# Display.net
KiCad netlist of a schematic drawn in Altium Designer
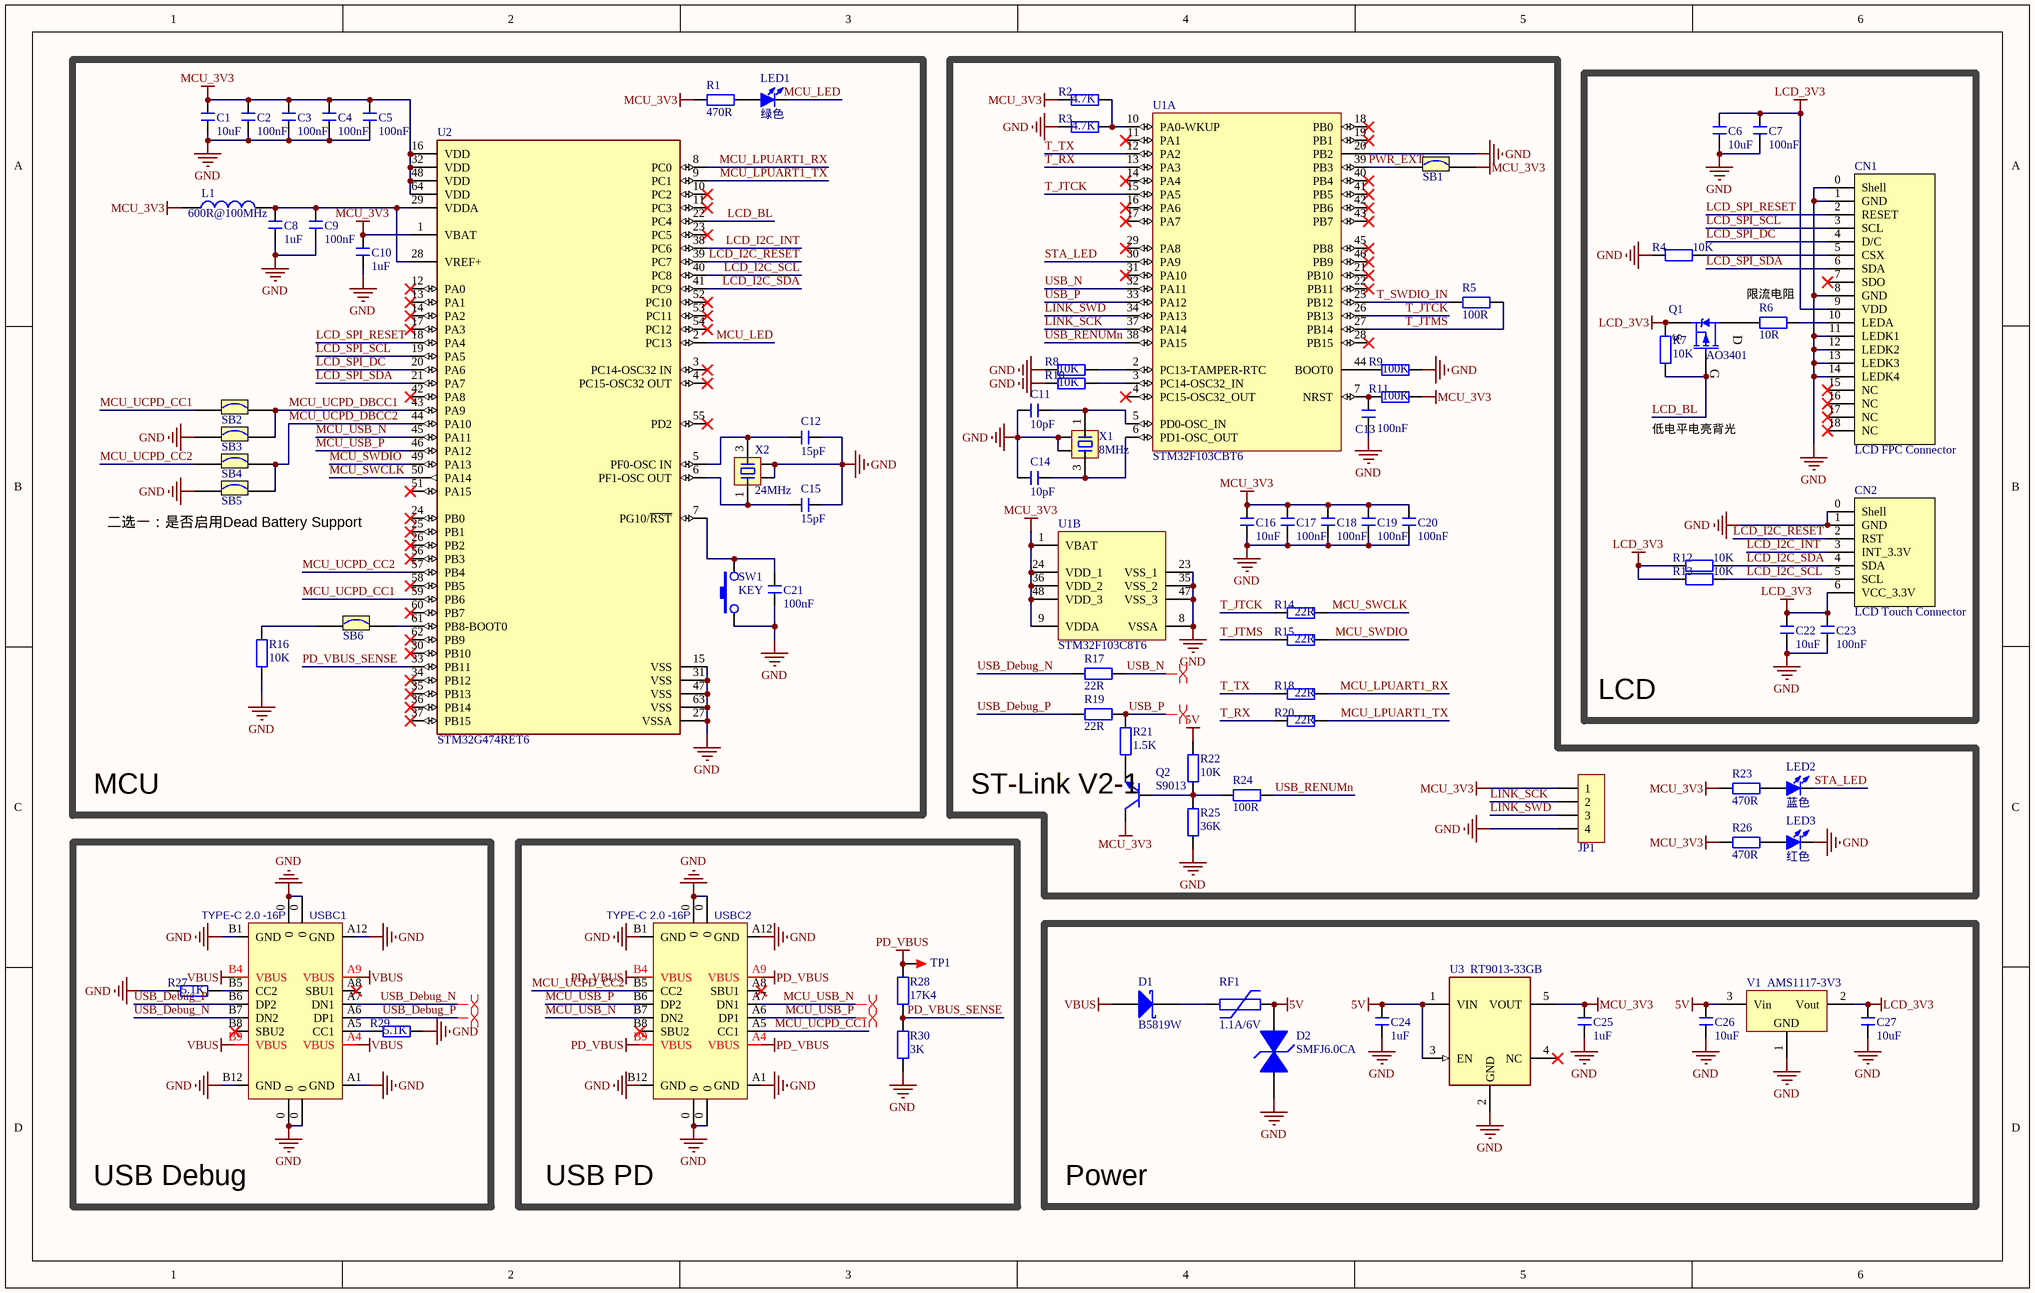
[diagram p0: Display.SchDoc]

(export (version "E")
  (design (tool "Eeschema 10.0.6"))
  (components
    (comp (ref "C1")
      (value "10uF")
      (footprint "C 0402_L")
      (description "无极性贴片电容")
      (fields (field (name "版权归属") "源创客"))
      (libsource (lib "源创客") (part "C"))
    )
    (comp (ref "C2")
      (value "100nF")
      (footprint "C 0402_L")
      (description "无极性贴片电容")
      (fields (field (name "版权归属") "源创客"))
      (libsource (lib "源创客") (part "C"))
    )
    (comp (ref "C3")
      (value "100nF")
      (footprint "C 0402_L")
      (description "无极性贴片电容")
      (fields (field (name "版权归属") "源创客"))
      (libsource (lib "源创客") (part "C"))
    )
    (comp (ref "C4")
      (value "100nF")
      (footprint "C 0402_L")
      (description "无极性贴片电容")
      (fields (field (name "版权归属") "源创客"))
      (libsource (lib "源创客") (part "C"))
    )
    (comp (ref "C5")
      (value "100nF")
      (footprint "C 0402_L")
      (description "无极性贴片电容")
      (fields (field (name "版权归属") "源创客"))
      (libsource (lib "源创客") (part "C"))
    )
    (comp (ref "C6")
      (value "10uF")
      (footprint "C 0402_L")
      (description "无极性贴片电容")
      (fields (field (name "版权归属") "源创客"))
      (libsource (lib "源创客") (part "C"))
    )
    (comp (ref "C7")
      (value "100nF")
      (footprint "C 0402_L")
      (description "无极性贴片电容")
      (fields (field (name "版权归属") "源创客"))
      (libsource (lib "源创客") (part "C"))
    )
    (comp (ref "C8")
      (value "1uF")
      (footprint "C 0402_L")
      (description "无极性贴片电容")
      (fields (field (name "版权归属") "源创客"))
      (libsource (lib "源创客") (part "C"))
    )
    (comp (ref "C9")
      (value "100nF")
      (footprint "C 0402_L")
      (description "无极性贴片电容")
      (fields (field (name "版权归属") "源创客"))
      (libsource (lib "源创客") (part "C"))
    )
    (comp (ref "C10")
      (value "1uF")
      (footprint "C 0402_L")
      (description "无极性贴片电容")
      (fields (field (name "版权归属") "源创客"))
      (libsource (lib "源创客") (part "C"))
    )
    (comp (ref "C11")
      (value "10pF")
      (footprint "C 0402_L")
      (description "无极性贴片电容")
      (fields (field (name "版权归属") "源创客"))
      (libsource (lib "源创客") (part "C"))
    )
    (comp (ref "C12")
      (value "15pF")
      (footprint "C 0402_L")
      (description "无极性贴片电容")
      (fields (field (name "版权归属") "源创客"))
      (libsource (lib "源创客") (part "C"))
    )
    (comp (ref "C13")
      (value "100nF")
      (footprint "C 0402_L")
      (description "无极性贴片电容")
      (fields (field (name "版权归属") "源创客"))
      (libsource (lib "源创客") (part "C"))
    )
    (comp (ref "C14")
      (value "10pF")
      (footprint "C 0402_L")
      (description "无极性贴片电容")
      (fields (field (name "版权归属") "源创客"))
      (libsource (lib "源创客") (part "C"))
    )
    (comp (ref "C15")
      (value "15pF")
      (footprint "C 0402_L")
      (description "无极性贴片电容")
      (fields (field (name "版权归属") "源创客"))
      (libsource (lib "源创客") (part "C"))
    )
    (comp (ref "C16")
      (value "10uF")
      (footprint "C 0402_L")
      (description "无极性贴片电容")
      (fields (field (name "版权归属") "源创客"))
      (libsource (lib "源创客") (part "C"))
    )
    (comp (ref "C17")
      (value "100nF")
      (footprint "C 0402_L")
      (description "无极性贴片电容")
      (fields (field (name "版权归属") "源创客"))
      (libsource (lib "源创客") (part "C"))
    )
    (comp (ref "C18")
      (value "100nF")
      (footprint "C 0402_L")
      (description "无极性贴片电容")
      (fields (field (name "版权归属") "源创客"))
      (libsource (lib "源创客") (part "C"))
    )
    (comp (ref "C19")
      (value "100nF")
      (footprint "C 0402_L")
      (description "无极性贴片电容")
      (fields (field (name "版权归属") "源创客"))
      (libsource (lib "源创客") (part "C"))
    )
    (comp (ref "C20")
      (value "100nF")
      (footprint "C 0402_L")
      (description "无极性贴片电容")
      (fields (field (name "版权归属") "源创客"))
      (libsource (lib "源创客") (part "C"))
    )
    (comp (ref "C21")
      (value "100nF")
      (footprint "C 0402_L")
      (description "无极性贴片电容")
      (fields (field (name "版权归属") "源创客"))
      (libsource (lib "源创客") (part "C"))
    )
    (comp (ref "C22")
      (value "10uF")
      (footprint "C 0402_L")
      (description "无极性贴片电容")
      (fields (field (name "版权归属") "源创客"))
      (libsource (lib "源创客") (part "C"))
    )
    (comp (ref "C23")
      (value "100nF")
      (footprint "C 0402_L")
      (description "无极性贴片电容")
      (fields (field (name "版权归属") "源创客"))
      (libsource (lib "源创客") (part "C"))
    )
    (comp (ref "C24")
      (value "1uF")
      (footprint "C 0402_L")
      (description "无极性贴片电容")
      (fields (field (name "版权归属") "源创客"))
      (libsource (lib "源创客") (part "C"))
    )
    (comp (ref "C25")
      (value "1uF")
      (footprint "C 0402_L")
      (description "无极性贴片电容")
      (fields (field (name "版权归属") "源创客"))
      (libsource (lib "源创客") (part "C"))
    )
    (comp (ref "C26")
      (value "10uF")
      (footprint "C 0402_L")
      (description "无极性贴片电容")
      (fields (field (name "版权归属") "源创客"))
      (libsource (lib "源创客") (part "C"))
    )
    (comp (ref "C27")
      (value "10uF")
      (footprint "C 0402_L")
      (description "无极性贴片电容")
      (fields (field (name "版权归属") "源创客"))
      (libsource (lib "源创客") (part "C"))
    )
    (comp (ref "CN1")
      (value "LCD FPC Connector")
      (footprint "FPC_Connector_0.5mm_18P")
      (description "2.8英寸TFT-LCD电容触摸屏接插式FPC座子")
      (libsource (lib "Display") (part "LCD"))
    )
    (comp (ref "CN2")
      (value "LCD Touch Connector")
      (footprint "FPC_Connector_0.5mm_6P")
      (description "2.8英寸TFT-LCD电容触摸屏触摸检测芯片接插式FPC座子")
      (libsource (lib "Display") (part "Touch"))
    )
    (comp (ref "D1")
      (value "B5819W")
      (footprint "MCC-SOD123_V")
      (description "Schottky Barrier Rectifier, 1 A, 40 Vrm, -65 to 125 degC, 2-Pin SOD123, RoHS, Tape and Reel")
      (fields (field (name "MANUFACTURER") "Micro Commercial Components"))
      (libsource (lib "Altium Content Vault") (part "DSKY-AK-2"))
    )
    (comp (ref "D2")
      (value "SMFJ6.0CA")
      (footprint "SMFJ6.0CA")
      (description "贴片TVS瞬变抑制二极管")
      (libsource (lib "Display") (part "SMFJ6.0CA"))
    )
    (comp (ref "JP1")
      (value "HDR-1X4")
      (footprint "HDR2.54-LI-4P")
      (description "4P接插件")
      (libsource (lib "5.5 - 2.54mm(100mil)连接器(XH2.54)") (part "Header 4"))
    )
    (comp (ref "L1")
      (value "600R@100MHz")
      (footprint "L 0603")
      (description "小功率贴片电感")
      (fields (field (name "版权归属") "源创客"))
      (libsource (lib "源创客") (part "L"))
    )
    (comp (ref "LED1")
      (value "绿色")
      (footprint "LED 0603G")
      (description "贴片LED")
      (fields (field (name "版权归属") "源创客"))
      (libsource (lib "源创客") (part "LED-SMD"))
    )
    (comp (ref "LED2")
      (value "蓝色")
      (footprint "LED 0603B")
      (description "贴片LED")
      (fields (field (name "版权归属") "源创客"))
      (libsource (lib "源创客") (part "LED-SMD"))
    )
    (comp (ref "LED3")
      (value "红色")
      (footprint "LED 0603R")
      (description "贴片LED")
      (fields (field (name "版权归属") "源创客"))
      (libsource (lib "源创客") (part "LED-SMD"))
    )
    (comp (ref "Q1")
      (value "AO3401")
      (footprint "SOT23-3L")
      (description "P沟道 30V/4.2A")
      (libsource (lib "0.4 - 三极管-场效应管-可控硅") (part "AO3401"))
    )
    (comp (ref "Q2")
      (value "S9013")
      (footprint "SOT23-3L")
      (description "低频放大-NPN型")
      (fields (field (name "版权归属") "源创客"))
      (libsource (lib "源创客") (part "9013-SMD"))
    )
    (comp (ref "R1")
      (value "470R")
      (footprint "R 0402_L")
      (description "贴片电阻")
      (fields (field (name "版权归属") "源创客"))
      (libsource (lib "源创客") (part "R"))
    )
    (comp (ref "R2")
      (value "4.7K")
      (footprint "R 0402_L")
      (description "贴片电阻")
      (fields (field (name "版权归属") "源创客"))
      (libsource (lib "源创客") (part "R"))
    )
    (comp (ref "R3")
      (value "4.7K")
      (footprint "R 0402_L")
      (description "贴片电阻")
      (fields (field (name "版权归属") "源创客"))
      (libsource (lib "源创客") (part "R"))
    )
    (comp (ref "R4")
      (value "10K")
      (footprint "R 0402_L")
      (description "贴片电阻")
      (fields (field (name "版权归属") "源创客"))
      (libsource (lib "源创客") (part "R"))
    )
    (comp (ref "R5")
      (value "100R")
      (footprint "R 0402_L")
      (description "贴片电阻")
      (fields (field (name "版权归属") "源创客"))
      (libsource (lib "源创客") (part "R"))
    )
    (comp (ref "R6")
      (value "10R")
      (footprint "R 0402_L")
      (description "贴片电阻")
      (fields (field (name "版权归属") "源创客"))
      (libsource (lib "源创客") (part "R"))
    )
    (comp (ref "R7")
      (value "10K")
      (footprint "R 0402_L")
      (description "贴片电阻")
      (fields (field (name "版权归属") "源创客"))
      (libsource (lib "源创客") (part "R"))
    )
    (comp (ref "R8")
      (value "10K")
      (footprint "R 0402_L")
      (description "贴片电阻")
      (fields (field (name "版权归属") "源创客"))
      (libsource (lib "源创客") (part "R"))
    )
    (comp (ref "R9")
      (value "100K")
      (footprint "R 0402_L")
      (description "贴片电阻")
      (fields (field (name "版权归属") "源创客"))
      (libsource (lib "源创客") (part "R"))
    )
    (comp (ref "R10")
      (value "10K")
      (footprint "R 0402_L")
      (description "贴片电阻")
      (fields (field (name "版权归属") "源创客"))
      (libsource (lib "源创客") (part "R"))
    )
    (comp (ref "R11")
      (value "100K")
      (footprint "R 0402_L")
      (description "贴片电阻")
      (fields (field (name "版权归属") "源创客"))
      (libsource (lib "源创客") (part "R"))
    )
    (comp (ref "R12")
      (value "10K")
      (footprint "R 0402_L")
      (description "贴片电阻")
      (fields (field (name "版权归属") "源创客"))
      (libsource (lib "源创客") (part "R"))
    )
    (comp (ref "R13")
      (value "10K")
      (footprint "R 0402_L")
      (description "贴片电阻")
      (fields (field (name "版权归属") "源创客"))
      (libsource (lib "源创客") (part "R"))
    )
    (comp (ref "R14")
      (value "22R")
      (footprint "R 0402_L")
      (description "贴片电阻")
      (fields (field (name "版权归属") "源创客"))
      (libsource (lib "源创客") (part "R"))
    )
    (comp (ref "R15")
      (value "22R")
      (footprint "R 0402_L")
      (description "贴片电阻")
      (fields (field (name "版权归属") "源创客"))
      (libsource (lib "源创客") (part "R"))
    )
    (comp (ref "R16")
      (value "10K")
      (footprint "R 0402_L")
      (description "贴片电阻")
      (fields (field (name "版权归属") "源创客"))
      (libsource (lib "源创客") (part "R"))
    )
    (comp (ref "R17")
      (value "22R")
      (footprint "R 0402_L")
      (description "贴片电阻")
      (fields (field (name "版权归属") "源创客"))
      (libsource (lib "源创客") (part "R"))
    )
    (comp (ref "R18")
      (value "22R")
      (footprint "R 0402_L")
      (description "贴片电阻")
      (fields (field (name "版权归属") "源创客"))
      (libsource (lib "源创客") (part "R"))
    )
    (comp (ref "R19")
      (value "22R")
      (footprint "R 0402_L")
      (description "贴片电阻")
      (fields (field (name "版权归属") "源创客"))
      (libsource (lib "源创客") (part "R"))
    )
    (comp (ref "R20")
      (value "22R")
      (footprint "R 0402_L")
      (description "贴片电阻")
      (fields (field (name "版权归属") "源创客"))
      (libsource (lib "源创客") (part "R"))
    )
    (comp (ref "R21")
      (value "1.5K")
      (footprint "R 0402_L")
      (description "贴片电阻")
      (fields (field (name "版权归属") "源创客"))
      (libsource (lib "源创客") (part "R"))
    )
    (comp (ref "R22")
      (value "10K")
      (footprint "R 0402_L")
      (description "贴片电阻")
      (fields (field (name "版权归属") "源创客"))
      (libsource (lib "源创客") (part "R"))
    )
    (comp (ref "R23")
      (value "470R")
      (footprint "R 0402_L")
      (description "贴片电阻")
      (fields (field (name "版权归属") "源创客"))
      (libsource (lib "源创客") (part "R"))
    )
    (comp (ref "R24")
      (value "100R")
      (footprint "R 0402_L")
      (description "贴片电阻")
      (fields (field (name "版权归属") "源创客"))
      (libsource (lib "源创客") (part "R"))
    )
    (comp (ref "R25")
      (value "36K")
      (footprint "R 0402_L")
      (description "贴片电阻")
      (fields (field (name "版权归属") "源创客"))
      (libsource (lib "源创客") (part "R"))
    )
    (comp (ref "R26")
      (value "470R")
      (footprint "R 0402_L")
      (description "贴片电阻")
      (fields (field (name "版权归属") "源创客"))
      (libsource (lib "源创客") (part "R"))
    )
    (comp (ref "R27")
      (value "5.1K")
      (footprint "R 0402_L")
      (description "贴片电阻")
      (fields (field (name "版权归属") "源创客"))
      (libsource (lib "源创客") (part "R"))
    )
    (comp (ref "R28")
      (value "17K4")
      (footprint "R 0402_L")
      (description "贴片电阻")
      (fields (field (name "版权归属") "源创客"))
      (libsource (lib "源创客") (part "R"))
    )
    (comp (ref "R29")
      (value "5.1K")
      (footprint "R 0402_L")
      (description "贴片电阻")
      (fields (field (name "版权归属") "源创客"))
      (libsource (lib "源创客") (part "R"))
    )
    (comp (ref "R30")
      (value "3K")
      (footprint "R 0402_L")
      (description "贴片电阻")
      (fields (field (name "版权归属") "源创客"))
      (libsource (lib "源创客") (part "R"))
    )
    (comp (ref "RF1")
      (value "1.1A/6V")
      (footprint "MF-NSMF110-2")
      (description "PPTC自恢复保险丝")
      (fields (field (name "版权归属") "源创客"))
      (libsource (lib "源创客") (part "PPTC"))
    )
    (comp (ref "SB1")
      (value "SelectBit")
      (footprint "SelectBit 0402")
      (description "跨接桥，用于选择不同的模式，可以用锡连上，或者焊上0R电阻")
      (libsource (lib "Display") (part "SelectBit"))
    )
    (comp (ref "SB2")
      (value "SelectBit")
      (footprint "SelectBit 0402")
      (description "跨接桥，用于选择不同的模式，可以用锡连上，或者焊上0R电阻")
      (libsource (lib "Display") (part "SelectBit"))
    )
    (comp (ref "SB3")
      (value "SelectBit")
      (footprint "SelectBit 0402")
      (description "跨接桥，用于选择不同的模式，可以用锡连上，或者焊上0R电阻")
      (libsource (lib "Display") (part "SelectBit"))
    )
    (comp (ref "SB4")
      (value "SelectBit")
      (footprint "SelectBit 0402")
      (description "跨接桥，用于选择不同的模式，可以用锡连上，或者焊上0R电阻")
      (libsource (lib "Display") (part "SelectBit"))
    )
    (comp (ref "SB5")
      (value "SelectBit")
      (footprint "SelectBit 0402")
      (description "跨接桥，用于选择不同的模式，可以用锡连上，或者焊上0R电阻")
      (libsource (lib "Display") (part "SelectBit"))
    )
    (comp (ref "SB6")
      (value "SelectBit")
      (footprint "SelectBit 0402")
      (description "跨接桥，用于选择不同的模式，可以用锡连上，或者焊上0R电阻")
      (libsource (lib "Display") (part "SelectBit"))
    )
    (comp (ref "SW1")
      (value "KEY")
      (footprint "小乌龟2脚轻触开关3.9*2.9")
      (description "轻触开关")
      (libsource (lib "轻触开关") (part "KEY"))
    )
    (comp (ref "TP1")
      (value "TEST TP")
      (footprint "TEST TP1.4_R")
      (description "测试环")
      (fields (field (name "版权归属") "源创客"))
      (libsource (lib "源创客") (part "TEST TP"))
    )
    (comp (ref "U1")
      (value "STM32F103CBT6")
      (footprint "STM-LQFP48_L")
      (fields (field (name "PARTNUMBER") "STM32F103C8T6"))
      (libsource (lib "Altium Content Vault") (part "MC-ARM-STM32F103X8_B-SQ48"))
    )
    (comp (ref "U2")
      (value "STM32G474RET6")
      (footprint "FP-LQFP64-5W-MFG")
      (description "MAINSTREAM ARM CORTEX-M4 CORE WI")
      (fields
        (field (name "MANUFACTURER") "STMicroelectronics")
        (field (name "OCTOPART") "https://octopart.com/stm32g474ret6-stmicroelectronics-102308483")
      )
      (libsource (lib "Altium Content Vault") (part "f7e4c2ab6713028e27effac94efeea5"))
    )
    (comp (ref "U3")
      (value "RT9013-33GB")
      (footprint "SOT94P279X129-5N")
      (description "Linear Voltage Regulator IC 1 Output 500mA SOT-23-5")
      (fields (field (name "MF") "Richtek USA"))
      (libsource (lib "Display") (part "RT9013-33GB"))
    )
    (comp (ref "USBC1")
      (value "TYPE-C 2.0 -16P")
      (footprint "USB-C-SMD_16P")
      (description "USB2.0_Type-C_16Pin母座")
      (libsource (lib "0.6 - 电源-以太网-音频-Type-C USB插座") (part "USB2.0_Type-C_16Pin"))
    )
    (comp (ref "USBC2")
      (value "TYPE-C 2.0 -16P")
      (footprint "USB-C-SMD_16P")
      (description "USB2.0_Type-C_16Pin母座")
      (libsource (lib "0.6 - 电源-以太网-音频-Type-C USB插座") (part "USB2.0_Type-C_16Pin"))
    )
    (comp (ref "V1")
      (value "AMS1117-3V3")
      (footprint "SOT89_L")
      (description "三端稳压芯片")
      (fields (field (name "版权归属") "源创客"))
      (libsource (lib "源创客") (part "AMS1117"))
    )
    (comp (ref "X1")
      (value "8MHz")
      (footprint "XTAL-3225-4P")
      (description "4脚无源晶振(谐振器）")
      (libsource (lib "0.1 - 电阻-电容-电感-晶振-晶体-磁珠-电位器") (part "XTAL-4P"))
    )
    (comp (ref "X2")
      (value "24MHz")
      (footprint "XTAL-3225-4P")
      (description "4脚无源晶振(谐振器）")
      (libsource (lib "") (part "XTAL-4P_1"))
    )
  )
  (nets
    (net (code "1") (name "/LCD_BL") (class "Default")
      (node (ref "Q1") (pin "1") (pinfunction "G_1") (pintype "passive"))
      (node (ref "R7") (pin "1") (pinfunction "1_1") (pintype "passive"))
      (node (ref "U2") (pin "22") (pinfunction "PC4_22") (pintype "bidirectional"))
    )
    (net (code "2") (name "/LCD_I2C_INT") (class "Default")
      (node (ref "CN2") (pin "3") (pinfunction "INT_3.3V_3") (pintype "passive"))
      (node (ref "U2") (pin "38") (pinfunction "PC6_38") (pintype "bidirectional"))
    )
    (net (code "3") (name "/LCD_I2C_RESET") (class "Default")
      (node (ref "CN2") (pin "2") (pinfunction "RST_2") (pintype "passive"))
      (node (ref "U2") (pin "39") (pinfunction "PC7_39") (pintype "bidirectional"))
    )
    (net (code "4") (name "/LCD_I2C_SCL") (class "Default")
      (node (ref "CN2") (pin "5") (pinfunction "SCL_5") (pintype "passive"))
      (node (ref "R13") (pin "1") (pinfunction "1_1") (pintype "passive"))
      (node (ref "U2") (pin "40") (pinfunction "PC8_40") (pintype "bidirectional"))
    )
    (net (code "5") (name "/LCD_I2C_SDA") (class "Default")
      (node (ref "CN2") (pin "4") (pinfunction "SDA_4") (pintype "passive"))
      (node (ref "R12") (pin "1") (pinfunction "1_1") (pintype "passive"))
      (node (ref "U2") (pin "41") (pinfunction "PC9_41") (pintype "bidirectional"))
    )
    (net (code "6") (name "/LCD_SPI_DC") (class "Default")
      (node (ref "CN1") (pin "4") (pinfunction "D/C_4") (pintype "passive"))
      (node (ref "U2") (pin "20") (pinfunction "PA6_20") (pintype "bidirectional"))
    )
    (net (code "7") (name "/LCD_SPI_RESET") (class "Default")
      (node (ref "CN1") (pin "2") (pinfunction "RESET_2") (pintype "passive"))
      (node (ref "U2") (pin "18") (pinfunction "PA4_18") (pintype "bidirectional"))
    )
    (net (code "8") (name "/LCD_SPI_SCL") (class "Default")
      (node (ref "CN1") (pin "3") (pinfunction "SCL_3") (pintype "passive"))
      (node (ref "U2") (pin "19") (pinfunction "PA5_19") (pintype "bidirectional"))
    )
    (net (code "9") (name "/LCD_SPI_SDA") (class "Default")
      (node (ref "CN1") (pin "6") (pinfunction "SDA_6") (pintype "passive"))
      (node (ref "U2") (pin "21") (pinfunction "PA7_21") (pintype "bidirectional"))
    )
    (net (code "10") (name "/LINK_SCK") (class "Default")
      (node (ref "JP1") (pin "2") (pinfunction "2_2") (pintype "passive"))
      (node (ref "U1") (pin "37") (pinfunction "PA14_37") (pintype "bidirectional"))
    )
    (net (code "11") (name "/LINK_SWD") (class "Default")
      (node (ref "JP1") (pin "3") (pinfunction "3_3") (pintype "passive"))
      (node (ref "U1") (pin "34") (pinfunction "PA13_34") (pintype "bidirectional"))
    )
    (net (code "12") (name "/MCU_LED") (class "Default")
      (node (ref "LED1") (pin "2") (pinfunction "K_2") (pintype "passive"))
      (node (ref "U2") (pin "2") (pinfunction "PC13_2") (pintype "bidirectional"))
    )
    (net (code "13") (name "/MCU_LPUART1_RX") (class "Default")
      (node (ref "R18") (pin "1") (pinfunction "1_1") (pintype "passive"))
      (node (ref "U2") (pin "8") (pinfunction "PC0_8") (pintype "bidirectional"))
    )
    (net (code "14") (name "/MCU_LPUART1_TX") (class "Default")
      (node (ref "R20") (pin "1") (pinfunction "1_1") (pintype "passive"))
      (node (ref "U2") (pin "9") (pinfunction "PC1_9") (pintype "bidirectional"))
    )
    (net (code "15") (name "/MCU_SWCLK") (class "Default")
      (node (ref "R14") (pin "1") (pinfunction "1_1") (pintype "passive"))
      (node (ref "U2") (pin "50") (pinfunction "PA14_50") (pintype "output"))
    )
    (net (code "16") (name "/MCU_SWDIO") (class "Default")
      (node (ref "R15") (pin "1") (pinfunction "1_1") (pintype "passive"))
      (node (ref "U2") (pin "49") (pinfunction "PA13_49") (pintype "bidirectional"))
    )
    (net (code "17") (name "/MCU_UCPD_CC1") (class "Default")
      (node (ref "SB2") (pin "1") (pinfunction "1_1") (pintype "passive"))
      (node (ref "U2") (pin "59") (pinfunction "PB6_59") (pintype "bidirectional"))
      (node (ref "USBC2") (pin "A5") (pinfunction "CC1_A5") (pintype "passive"))
    )
    (net (code "18") (name "/MCU_UCPD_CC2") (class "Default")
      (node (ref "SB4") (pin "1") (pinfunction "1_1") (pintype "passive"))
      (node (ref "U2") (pin "57") (pinfunction "PB4_57") (pintype "bidirectional"))
      (node (ref "USBC2") (pin "B5") (pinfunction "CC2_B5") (pintype "passive"))
    )
    (net (code "19") (name "/MCU_UCPD_DBCC1") (class "Default")
      (node (ref "SB2") (pin "2") (pinfunction "2_2") (pintype "passive"))
      (node (ref "SB3") (pin "2") (pinfunction "2_2") (pintype "passive"))
      (node (ref "U2") (pin "43") (pinfunction "PA9_43") (pintype "bidirectional"))
    )
    (net (code "20") (name "/MCU_UCPD_DBCC2") (class "Default")
      (node (ref "SB4") (pin "2") (pinfunction "2_2") (pintype "passive"))
      (node (ref "SB5") (pin "2") (pinfunction "2_2") (pintype "passive"))
      (node (ref "U2") (pin "44") (pinfunction "PA10_44") (pintype "bidirectional"))
    )
    (net (code "21") (name "/MCU_USB_N") (class "Default")
      (node (ref "U2") (pin "45") (pinfunction "PA11_45") (pintype "bidirectional"))
      (node (ref "USBC2") (pin "A7") (pinfunction "DN1_A7") (pintype "passive"))
      (node (ref "USBC2") (pin "B7") (pinfunction "DN2_B7") (pintype "passive"))
    )
    (net (code "22") (name "/MCU_USB_P") (class "Default")
      (node (ref "U2") (pin "46") (pinfunction "PA12_46") (pintype "bidirectional"))
      (node (ref "USBC2") (pin "A6") (pinfunction "DP1_A6") (pintype "passive"))
      (node (ref "USBC2") (pin "B6") (pinfunction "DP2_B6") (pintype "passive"))
    )
    (net (code "23") (name "/PD_VBUS_SENSE") (class "Default")
      (node (ref "R28") (pin "2") (pinfunction "2_2") (pintype "passive"))
      (node (ref "R30") (pin "1") (pinfunction "1_1") (pintype "passive"))
      (node (ref "U2") (pin "33") (pinfunction "PB11_33") (pintype "bidirectional"))
    )
    (net (code "24") (name "/PWR_EXT") (class "Default")
      (node (ref "SB1") (pin "1") (pinfunction "1_1") (pintype "passive"))
      (node (ref "U1") (pin "39") (pinfunction "PB3_39") (pintype "bidirectional"))
    )
    (net (code "25") (name "/STA_LED") (class "Default")
      (node (ref "LED2") (pin "2") (pinfunction "K_2") (pintype "passive"))
      (node (ref "U1") (pin "30") (pinfunction "PA9_30") (pintype "bidirectional"))
    )
    (net (code "26") (name "/T_JTCK") (class "Default")
      (node (ref "R14") (pin "2") (pinfunction "2_2") (pintype "passive"))
      (node (ref "U1") (pin "15") (pinfunction "PA5_15") (pintype "bidirectional"))
      (node (ref "U1") (pin "26") (pinfunction "PB13_26") (pintype "bidirectional"))
    )
    (net (code "27") (name "/T_JTMS") (class "Default")
      (node (ref "R15") (pin "2") (pinfunction "2_2") (pintype "passive"))
      (node (ref "R5") (pin "1") (pinfunction "1_1") (pintype "passive"))
      (node (ref "U1") (pin "27") (pinfunction "PB14_27") (pintype "bidirectional"))
    )
    (net (code "28") (name "/T_RX") (class "Default")
      (node (ref "R20") (pin "2") (pinfunction "2_2") (pintype "passive"))
      (node (ref "U1") (pin "13") (pinfunction "PA3_13") (pintype "bidirectional"))
    )
    (net (code "29") (name "/T_SWDIO_IN") (class "Default")
      (node (ref "R5") (pin "2") (pinfunction "2_2") (pintype "passive"))
      (node (ref "U1") (pin "25") (pinfunction "PB12_25") (pintype "bidirectional"))
    )
    (net (code "30") (name "/T_TX") (class "Default")
      (node (ref "R18") (pin "2") (pinfunction "2_2") (pintype "passive"))
      (node (ref "U1") (pin "12") (pinfunction "PA2_12") (pintype "bidirectional"))
    )
    (net (code "31") (name "/USB_Debug_N") (class "Default")
      (node (ref "R17") (pin "1") (pinfunction "1_1") (pintype "passive"))
      (node (ref "USBC1") (pin "A7") (pinfunction "DN1_A7") (pintype "passive"))
      (node (ref "USBC1") (pin "B7") (pinfunction "DN2_B7") (pintype "passive"))
    )
    (net (code "32") (name "/USB_Debug_P") (class "Default")
      (node (ref "R19") (pin "1") (pinfunction "1_1") (pintype "passive"))
      (node (ref "USBC1") (pin "A6") (pinfunction "DP1_A6") (pintype "passive"))
      (node (ref "USBC1") (pin "B6") (pinfunction "DP2_B6") (pintype "passive"))
    )
    (net (code "33") (name "/USB_N") (class "Default")
      (node (ref "R17") (pin "2") (pinfunction "2_2") (pintype "passive"))
      (node (ref "U1") (pin "32") (pinfunction "PA11_32") (pintype "bidirectional"))
    )
    (net (code "34") (name "/USB_P") (class "Default")
      (node (ref "R19") (pin "2") (pinfunction "2_2") (pintype "passive"))
      (node (ref "R21") (pin "2") (pinfunction "2_2") (pintype "passive"))
      (node (ref "U1") (pin "33") (pinfunction "PA12_33") (pintype "bidirectional"))
    )
    (net (code "35") (name "/USB_RENUMn") (class "Default")
      (node (ref "R24") (pin "1") (pinfunction "1_1") (pintype "passive"))
      (node (ref "U1") (pin "38") (pinfunction "PA15_38") (pintype "bidirectional"))
    )
    (net (code "36") (name "5V") (class "Default")
      (node (ref "C24") (pin "2") (pinfunction "2_2") (pintype "passive"))
      (node (ref "C26") (pin "2") (pinfunction "2_2") (pintype "passive"))
      (node (ref "D2") (pin "2") (pinfunction "2_2") (pintype "passive"))
      (node (ref "R22") (pin "2") (pinfunction "2_2") (pintype "passive"))
      (node (ref "RF1") (pin "2") (pinfunction "2_2") (pintype "passive"))
      (node (ref "U3") (pin "1") (pinfunction "VIN_1") (pintype "power_in"))
      (node (ref "U3") (pin "3") (pinfunction "EN_3") (pintype "input"))
      (node (ref "V1") (pin "3") (pinfunction "Vin_3") (pintype "passive"))
    )
    (net (code "37") (name "GND") (class "Default")
      (node (ref "C1") (pin "1") (pinfunction "1_1") (pintype "passive"))
      (node (ref "C10") (pin "1") (pinfunction "1_1") (pintype "passive"))
      (node (ref "C11") (pin "2") (pinfunction "2_2") (pintype "passive"))
      (node (ref "C12") (pin "1") (pinfunction "1_1") (pintype "passive"))
      (node (ref "C13") (pin "1") (pinfunction "1_1") (pintype "passive"))
      (node (ref "C14") (pin "2") (pinfunction "2_2") (pintype "passive"))
      (node (ref "C15") (pin "1") (pinfunction "1_1") (pintype "passive"))
      (node (ref "C16") (pin "1") (pinfunction "1_1") (pintype "passive"))
      (node (ref "C17") (pin "1") (pinfunction "1_1") (pintype "passive"))
      (node (ref "C18") (pin "1") (pinfunction "1_1") (pintype "passive"))
      (node (ref "C19") (pin "1") (pinfunction "1_1") (pintype "passive"))
      (node (ref "C2") (pin "1") (pinfunction "1_1") (pintype "passive"))
      (node (ref "C20") (pin "1") (pinfunction "1_1") (pintype "passive"))
      (node (ref "C21") (pin "2") (pinfunction "2_2") (pintype "passive"))
      (node (ref "C22") (pin "1") (pinfunction "1_1") (pintype "passive"))
      (node (ref "C23") (pin "1") (pinfunction "1_1") (pintype "passive"))
      (node (ref "C24") (pin "1") (pinfunction "1_1") (pintype "passive"))
      (node (ref "C25") (pin "1") (pinfunction "1_1") (pintype "passive"))
      (node (ref "C26") (pin "1") (pinfunction "1_1") (pintype "passive"))
      (node (ref "C27") (pin "1") (pinfunction "1_1") (pintype "passive"))
      (node (ref "C3") (pin "1") (pinfunction "1_1") (pintype "passive"))
      (node (ref "C4") (pin "1") (pinfunction "1_1") (pintype "passive"))
      (node (ref "C5") (pin "1") (pinfunction "1_1") (pintype "passive"))
      (node (ref "C6") (pin "1") (pinfunction "1_1") (pintype "passive"))
      (node (ref "C7") (pin "1") (pinfunction "1_1") (pintype "passive"))
      (node (ref "C8") (pin "1") (pinfunction "1_1") (pintype "passive"))
      (node (ref "C9") (pin "1") (pinfunction "1_1") (pintype "passive"))
      (node (ref "CN1") (pin "0") (pinfunction "Shell_0") (pintype "passive"))
      (node (ref "CN1") (pin "1") (pinfunction "GND_1") (pintype "passive"))
      (node (ref "CN1") (pin "11") (pinfunction "LEDK1_11") (pintype "passive"))
      (node (ref "CN1") (pin "12") (pinfunction "LEDK2_12") (pintype "passive"))
      (node (ref "CN1") (pin "13") (pinfunction "LEDK3_13") (pintype "passive"))
      (node (ref "CN1") (pin "14") (pinfunction "LEDK4_14") (pintype "passive"))
      (node (ref "CN1") (pin "8") (pinfunction "GND_8") (pintype "passive"))
      (node (ref "CN2") (pin "0") (pinfunction "Shell_0") (pintype "passive"))
      (node (ref "CN2") (pin "1") (pinfunction "GND_1") (pintype "passive"))
      (node (ref "D2") (pin "1") (pinfunction "1_1") (pintype "passive"))
      (node (ref "JP1") (pin "4") (pinfunction "4_4") (pintype "passive"))
      (node (ref "LED3") (pin "2") (pinfunction "K_2") (pintype "passive"))
      (node (ref "R10") (pin "2") (pinfunction "2_2") (pintype "passive"))
      (node (ref "R16") (pin "2") (pinfunction "2_2") (pintype "passive"))
      (node (ref "R25") (pin "1") (pinfunction "1_1") (pintype "passive"))
      (node (ref "R27") (pin "2") (pinfunction "2_2") (pintype "passive"))
      (node (ref "R29") (pin "1") (pinfunction "1_1") (pintype "passive"))
      (node (ref "R3") (pin "1") (pinfunction "1_1") (pintype "passive"))
      (node (ref "R30") (pin "2") (pinfunction "2_2") (pintype "passive"))
      (node (ref "R4") (pin "1") (pinfunction "1_1") (pintype "passive"))
      (node (ref "R8") (pin "2") (pinfunction "2_2") (pintype "passive"))
      (node (ref "R9") (pin "1") (pinfunction "1_1") (pintype "passive"))
      (node (ref "SB3") (pin "1") (pinfunction "1_1") (pintype "passive"))
      (node (ref "SB5") (pin "1") (pinfunction "1_1") (pintype "passive"))
      (node (ref "SW1") (pin "1") (pinfunction "1_1") (pintype "passive"))
      (node (ref "U1") (pin "20") (pinfunction "PB2_20") (pintype "bidirectional"))
      (node (ref "U1") (pin "23") (pinfunction "VSS_1_23") (pintype "power_in"))
      (node (ref "U1") (pin "35") (pinfunction "VSS_2_35") (pintype "power_in"))
      (node (ref "U1") (pin "47") (pinfunction "VSS_3_47") (pintype "power_in"))
      (node (ref "U1") (pin "8") (pinfunction "VSSA_8") (pintype "power_in"))
      (node (ref "U2") (pin "15") (pinfunction "VSS_15") (pintype "power_in"))
      (node (ref "U2") (pin "27") (pinfunction "VSSA_27") (pintype "power_in"))
      (node (ref "U2") (pin "31") (pinfunction "VSS_31") (pintype "power_in"))
      (node (ref "U2") (pin "47") (pinfunction "VSS_47") (pintype "power_in"))
      (node (ref "U2") (pin "63") (pinfunction "VSS_63") (pintype "power_in"))
      (node (ref "U3") (pin "2") (pinfunction "GND_2") (pintype "power_in"))
      (node (ref "USBC1") (pin "0") (pinfunction "0_0") (pintype "passive"))
      (node (ref "USBC1") (pin "A1") (pinfunction "GND_A1") (pintype "passive"))
      (node (ref "USBC1") (pin "A12") (pinfunction "GND_A12") (pintype "passive"))
      (node (ref "USBC1") (pin "B1") (pinfunction "GND_B1") (pintype "passive"))
      (node (ref "USBC1") (pin "B12") (pinfunction "GND_B12") (pintype "passive"))
      (node (ref "USBC2") (pin "0") (pinfunction "0_0") (pintype "passive"))
      (node (ref "USBC2") (pin "A1") (pinfunction "GND_A1") (pintype "passive"))
      (node (ref "USBC2") (pin "A12") (pinfunction "GND_A12") (pintype "passive"))
      (node (ref "USBC2") (pin "B1") (pinfunction "GND_B1") (pintype "passive"))
      (node (ref "USBC2") (pin "B12") (pinfunction "GND_B12") (pintype "passive"))
      (node (ref "V1") (pin "1") (pinfunction "GND_1") (pintype "passive"))
      (node (ref "X1") (pin "2") (pinfunction "2_2") (pintype "passive"))
      (node (ref "X1") (pin "4") (pinfunction "4_4") (pintype "passive"))
      (node (ref "X2") (pin "2") (pinfunction "2_2") (pintype "passive"))
      (node (ref "X2") (pin "4") (pinfunction "4_4") (pintype "passive"))
    )
    (net (code "38") (name "LCD_3V3") (class "Default")
      (node (ref "C22") (pin "2") (pinfunction "2_2") (pintype "passive"))
      (node (ref "C23") (pin "2") (pinfunction "2_2") (pintype "passive"))
      (node (ref "C27") (pin "2") (pinfunction "2_2") (pintype "passive"))
      (node (ref "C6") (pin "2") (pinfunction "2_2") (pintype "passive"))
      (node (ref "C7") (pin "2") (pinfunction "2_2") (pintype "passive"))
      (node (ref "CN1") (pin "9") (pinfunction "VDD_9") (pintype "passive"))
      (node (ref "CN2") (pin "6") (pinfunction "VCC_3.3V_6") (pintype "passive"))
      (node (ref "Q1") (pin "2") (pinfunction "S_2") (pintype "passive"))
      (node (ref "R12") (pin "2") (pinfunction "2_2") (pintype "passive"))
      (node (ref "R13") (pin "2") (pinfunction "2_2") (pintype "passive"))
      (node (ref "R7") (pin "2") (pinfunction "2_2") (pintype "passive"))
      (node (ref "V1") (pin "2") (pinfunction "Vout_2") (pintype "passive"))
    )
    (net (code "39") (name "MCU_3V3") (class "Default")
      (node (ref "C1") (pin "2") (pinfunction "2_2") (pintype "passive"))
      (node (ref "C10") (pin "2") (pinfunction "2_2") (pintype "passive"))
      (node (ref "C16") (pin "2") (pinfunction "2_2") (pintype "passive"))
      (node (ref "C17") (pin "2") (pinfunction "2_2") (pintype "passive"))
      (node (ref "C18") (pin "2") (pinfunction "2_2") (pintype "passive"))
      (node (ref "C19") (pin "2") (pinfunction "2_2") (pintype "passive"))
      (node (ref "C2") (pin "2") (pinfunction "2_2") (pintype "passive"))
      (node (ref "C20") (pin "2") (pinfunction "2_2") (pintype "passive"))
      (node (ref "C25") (pin "2") (pinfunction "2_2") (pintype "passive"))
      (node (ref "C3") (pin "2") (pinfunction "2_2") (pintype "passive"))
      (node (ref "C4") (pin "2") (pinfunction "2_2") (pintype "passive"))
      (node (ref "C5") (pin "2") (pinfunction "2_2") (pintype "passive"))
      (node (ref "JP1") (pin "1") (pinfunction "1_1") (pintype "passive"))
      (node (ref "L1") (pin "1") (pinfunction "1_1") (pintype "passive"))
      (node (ref "Q2") (pin "3") (pinfunction "C_3") (pintype "passive"))
      (node (ref "R1") (pin "2") (pinfunction "2_2") (pintype "passive"))
      (node (ref "R11") (pin "1") (pinfunction "1_1") (pintype "passive"))
      (node (ref "R2") (pin "1") (pinfunction "1_1") (pintype "passive"))
      (node (ref "R23") (pin "2") (pinfunction "2_2") (pintype "passive"))
      (node (ref "R26") (pin "2") (pinfunction "2_2") (pintype "passive"))
      (node (ref "SB1") (pin "2") (pinfunction "2_2") (pintype "passive"))
      (node (ref "U1") (pin "1") (pinfunction "VBAT_1") (pintype "power_in"))
      (node (ref "U1") (pin "24") (pinfunction "VDD_1_24") (pintype "power_in"))
      (node (ref "U1") (pin "36") (pinfunction "VDD_2_36") (pintype "power_in"))
      (node (ref "U1") (pin "48") (pinfunction "VDD_3_48") (pintype "power_in"))
      (node (ref "U1") (pin "9") (pinfunction "VDDA_9") (pintype "power_in"))
      (node (ref "U2") (pin "1") (pinfunction "VBAT_1") (pintype "power_in"))
      (node (ref "U2") (pin "16") (pinfunction "VDD_16") (pintype "power_in"))
      (node (ref "U2") (pin "32") (pinfunction "VDD_32") (pintype "power_in"))
      (node (ref "U2") (pin "48") (pinfunction "VDD_48") (pintype "power_in"))
      (node (ref "U2") (pin "64") (pinfunction "VDD_64") (pintype "power_in"))
      (node (ref "U3") (pin "5") (pinfunction "VOUT_5") (pintype "passive"))
    )
    (net (code "40") (name "Net-(CN1-CSX)") (class "Default")
      (node (ref "CN1") (pin "5") (pinfunction "CSX_5") (pintype "passive"))
      (node (ref "R4") (pin "2") (pinfunction "2_2") (pintype "passive"))
    )
    (net (code "41") (name "Net-(CN1-LEDA)") (class "Default")
      (node (ref "CN1") (pin "10") (pinfunction "LEDA_10") (pintype "passive"))
      (node (ref "R6") (pin "2") (pinfunction "2_2") (pintype "passive"))
    )
    (net (code "42") (name "Net-(D1-K)") (class "Default")
      (node (ref "D1") (pin "2") (pinfunction "K_2") (pintype "passive"))
      (node (ref "RF1") (pin "1") (pinfunction "1_1") (pintype "passive"))
    )
    (net (code "43") (name "Net-(LED1-A)") (class "Default")
      (node (ref "LED1") (pin "1") (pinfunction "A_1") (pintype "passive"))
      (node (ref "R1") (pin "1") (pinfunction "1_1") (pintype "passive"))
    )
    (net (code "44") (name "Net-(LED2-A)") (class "Default")
      (node (ref "LED2") (pin "1") (pinfunction "A_1") (pintype "passive"))
      (node (ref "R23") (pin "1") (pinfunction "1_1") (pintype "passive"))
    )
    (net (code "45") (name "Net-(LED3-A)") (class "Default")
      (node (ref "LED3") (pin "1") (pinfunction "A_1") (pintype "passive"))
      (node (ref "R26") (pin "1") (pinfunction "1_1") (pintype "passive"))
    )
    (net (code "46") (name "Net-(Q1-D)") (class "Default")
      (node (ref "Q1") (pin "3") (pinfunction "D_3") (pintype "passive"))
      (node (ref "R6") (pin "1") (pinfunction "1_1") (pintype "passive"))
    )
    (net (code "47") (name "Net-(Q2-B)") (class "Default")
      (node (ref "Q2") (pin "1") (pinfunction "B_1") (pintype "passive"))
      (node (ref "R22") (pin "1") (pinfunction "1_1") (pintype "passive"))
      (node (ref "R24") (pin "2") (pinfunction "2_2") (pintype "passive"))
      (node (ref "R25") (pin "2") (pinfunction "2_2") (pintype "passive"))
    )
    (net (code "48") (name "Net-(Q2-E)") (class "Default")
      (node (ref "Q2") (pin "2") (pinfunction "E_2") (pintype "passive"))
      (node (ref "R21") (pin "1") (pinfunction "1_1") (pintype "passive"))
    )
    (net (code "49") (name "Net-(R16-Pad1)") (class "Default")
      (node (ref "R16") (pin "1") (pinfunction "1_1") (pintype "passive"))
      (node (ref "SB6") (pin "1") (pinfunction "1_1") (pintype "passive"))
    )
    (net (code "50") (name "Net-(U1A-BOOT0)") (class "Default")
      (node (ref "R9") (pin "2") (pinfunction "2_2") (pintype "passive"))
      (node (ref "U1") (pin "44") (pinfunction "BOOT0_44") (pintype "input"))
    )
    (net (code "51") (name "Net-(U1A-NRST)") (class "Default")
      (node (ref "C13") (pin "2") (pinfunction "2_2") (pintype "passive"))
      (node (ref "R11") (pin "2") (pinfunction "2_2") (pintype "passive"))
      (node (ref "U1") (pin "7") (pinfunction "NRST_7") (pintype "bidirectional"))
    )
    (net (code "52") (name "Net-(U1A-PA0-WKUP)") (class "Default")
      (node (ref "R2") (pin "2") (pinfunction "2_2") (pintype "passive"))
      (node (ref "R3") (pin "2") (pinfunction "2_2") (pintype "passive"))
      (node (ref "U1") (pin "10") (pinfunction "PA0-WKUP_10") (pintype "bidirectional"))
    )
    (net (code "53") (name "Net-(U1A-PC13-TAMPER-RTC)") (class "Default")
      (node (ref "R8") (pin "1") (pinfunction "1_1") (pintype "passive"))
      (node (ref "U1") (pin "2") (pinfunction "PC13-TAMPER-RTC_2") (pintype "bidirectional"))
    )
    (net (code "54") (name "Net-(U1A-PC14-OSC32_IN)") (class "Default")
      (node (ref "R10") (pin "1") (pinfunction "1_1") (pintype "passive"))
      (node (ref "U1") (pin "3") (pinfunction "PC14-OSC32_IN_3") (pintype "bidirectional"))
    )
    (net (code "55") (name "Net-(U1A-PD0-OSC_IN)") (class "Default")
      (node (ref "C11") (pin "1") (pinfunction "1_1") (pintype "passive"))
      (node (ref "U1") (pin "5") (pinfunction "PD0-OSC_IN_5") (pintype "bidirectional"))
      (node (ref "X1") (pin "1") (pinfunction "1_1") (pintype "passive"))
    )
    (net (code "56") (name "Net-(U1A-PD1-OSC_OUT)") (class "Default")
      (node (ref "C14") (pin "1") (pinfunction "1_1") (pintype "passive"))
      (node (ref "U1") (pin "6") (pinfunction "PD1-OSC_OUT_6") (pintype "bidirectional"))
      (node (ref "X1") (pin "3") (pinfunction "3_3") (pintype "passive"))
    )
    (net (code "57") (name "Net-(U2-PB8-BOOT0)") (class "Default")
      (node (ref "SB6") (pin "2") (pinfunction "2_2") (pintype "passive"))
      (node (ref "U2") (pin "61") (pinfunction "PB8-BOOT0_61") (pintype "bidirectional"))
    )
    (net (code "58") (name "Net-(U2-PF0-OSC_IN)") (class "Default")
      (node (ref "C12") (pin "2") (pinfunction "2_2") (pintype "passive"))
      (node (ref "U2") (pin "5") (pinfunction "PF0-OSC_IN_5") (pintype "bidirectional"))
      (node (ref "X2") (pin "3") (pinfunction "3_3") (pintype "passive"))
    )
    (net (code "59") (name "Net-(U2-PF1-OSC_OUT)") (class "Default")
      (node (ref "C15") (pin "2") (pinfunction "2_2") (pintype "passive"))
      (node (ref "U2") (pin "6") (pinfunction "PF1-OSC_OUT_6") (pintype "bidirectional"))
      (node (ref "X2") (pin "1") (pinfunction "1_1") (pintype "passive"))
    )
    (net (code "60") (name "Net-(U2-PG10{slash}~{RST})") (class "Default")
      (node (ref "C21") (pin "1") (pinfunction "1_1") (pintype "passive"))
      (node (ref "SW1") (pin "3") (pinfunction "3_3") (pintype "passive"))
      (node (ref "U2") (pin "7") (pinfunction "PG10/~{RST}_7") (pintype "bidirectional"))
    )
    (net (code "61") (name "Net-(U2-VDDA)") (class "Default")
      (node (ref "C8") (pin "2") (pinfunction "2_2") (pintype "passive"))
      (node (ref "C9") (pin "2") (pinfunction "2_2") (pintype "passive"))
      (node (ref "L1") (pin "2") (pinfunction "2_2") (pintype "passive"))
      (node (ref "U2") (pin "28") (pinfunction "VREF+_28") (pintype "power_in"))
      (node (ref "U2") (pin "29") (pinfunction "VDDA_29") (pintype "power_in"))
    )
    (net (code "62") (name "Net-(USBC1-CC1)") (class "Default")
      (node (ref "R29") (pin "2") (pinfunction "2_2") (pintype "passive"))
      (node (ref "USBC1") (pin "A5") (pinfunction "CC1_A5") (pintype "passive"))
    )
    (net (code "63") (name "Net-(USBC1-CC2)") (class "Default")
      (node (ref "R27") (pin "1") (pinfunction "1_1") (pintype "passive"))
      (node (ref "USBC1") (pin "B5") (pinfunction "CC2_B5") (pintype "passive"))
    )
    (net (code "64") (name "PD_VBUS") (class "Default")
      (node (ref "R28") (pin "1") (pinfunction "1_1") (pintype "passive"))
      (node (ref "TP1") (pin "1") (pinfunction "1_1") (pintype "passive"))
      (node (ref "USBC2") (pin "A4") (pinfunction "VBUS_A4") (pintype "passive"))
      (node (ref "USBC2") (pin "A9") (pinfunction "VBUS_A9") (pintype "passive"))
      (node (ref "USBC2") (pin "B4") (pinfunction "VBUS_B4") (pintype "passive"))
      (node (ref "USBC2") (pin "B9") (pinfunction "VBUS_B9") (pintype "passive"))
    )
    (net (code "65") (name "VBUS") (class "Default")
      (node (ref "D1") (pin "1") (pinfunction "A_1") (pintype "passive"))
      (node (ref "USBC1") (pin "A4") (pinfunction "VBUS_A4") (pintype "passive"))
      (node (ref "USBC1") (pin "A9") (pinfunction "VBUS_A9") (pintype "passive"))
      (node (ref "USBC1") (pin "B4") (pinfunction "VBUS_B4") (pintype "passive"))
      (node (ref "USBC1") (pin "B9") (pinfunction "VBUS_B9") (pintype "passive"))
    )
    (net (code "66") (name "unconnected-(CN1-NC-Pad15)") (class "Default")
      (node (ref "CN1") (pin "15") (pinfunction "NC_15") (pintype "passive+no_connect"))
    )
    (net (code "67") (name "unconnected-(CN1-NC-Pad16)") (class "Default")
      (node (ref "CN1") (pin "16") (pinfunction "NC_16") (pintype "passive+no_connect"))
    )
    (net (code "68") (name "unconnected-(CN1-NC-Pad17)") (class "Default")
      (node (ref "CN1") (pin "17") (pinfunction "NC_17") (pintype "passive+no_connect"))
    )
    (net (code "69") (name "unconnected-(CN1-NC-Pad18)") (class "Default")
      (node (ref "CN1") (pin "18") (pinfunction "NC_18") (pintype "passive+no_connect"))
    )
    (net (code "70") (name "unconnected-(CN1-SDO-Pad7)") (class "Default")
      (node (ref "CN1") (pin "7") (pinfunction "SDO_7") (pintype "passive+no_connect"))
    )
    (net (code "71") (name "unconnected-(U1A-PA1-Pad11)") (class "Default")
      (node (ref "U1") (pin "11") (pinfunction "PA1_11") (pintype "bidirectional+no_connect"))
    )
    (net (code "72") (name "unconnected-(U1A-PA4-Pad14)") (class "Default")
      (node (ref "U1") (pin "14") (pinfunction "PA4_14") (pintype "bidirectional+no_connect"))
    )
    (net (code "73") (name "unconnected-(U1A-PA6-Pad16)") (class "Default")
      (node (ref "U1") (pin "16") (pinfunction "PA6_16") (pintype "bidirectional+no_connect"))
    )
    (net (code "74") (name "unconnected-(U1A-PA7-Pad17)") (class "Default")
      (node (ref "U1") (pin "17") (pinfunction "PA7_17") (pintype "bidirectional+no_connect"))
    )
    (net (code "75") (name "unconnected-(U1A-PA8-Pad29)") (class "Default")
      (node (ref "U1") (pin "29") (pinfunction "PA8_29") (pintype "bidirectional+no_connect"))
    )
    (net (code "76") (name "unconnected-(U1A-PA10-Pad31)") (class "Default")
      (node (ref "U1") (pin "31") (pinfunction "PA10_31") (pintype "bidirectional+no_connect"))
    )
    (net (code "77") (name "unconnected-(U1A-PB0-Pad18)") (class "Default")
      (node (ref "U1") (pin "18") (pinfunction "PB0_18") (pintype "bidirectional+no_connect"))
    )
    (net (code "78") (name "unconnected-(U1A-PB1-Pad19)") (class "Default")
      (node (ref "U1") (pin "19") (pinfunction "PB1_19") (pintype "bidirectional+no_connect"))
    )
    (net (code "79") (name "unconnected-(U1A-PB4-Pad40)") (class "Default")
      (node (ref "U1") (pin "40") (pinfunction "PB4_40") (pintype "bidirectional+no_connect"))
    )
    (net (code "80") (name "unconnected-(U1A-PB5-Pad41)") (class "Default")
      (node (ref "U1") (pin "41") (pinfunction "PB5_41") (pintype "bidirectional+no_connect"))
    )
    (net (code "81") (name "unconnected-(U1A-PB6-Pad42)") (class "Default")
      (node (ref "U1") (pin "42") (pinfunction "PB6_42") (pintype "bidirectional+no_connect"))
    )
    (net (code "82") (name "unconnected-(U1A-PB7-Pad43)") (class "Default")
      (node (ref "U1") (pin "43") (pinfunction "PB7_43") (pintype "bidirectional+no_connect"))
    )
    (net (code "83") (name "unconnected-(U1A-PB8-Pad45)") (class "Default")
      (node (ref "U1") (pin "45") (pinfunction "PB8_45") (pintype "bidirectional+no_connect"))
    )
    (net (code "84") (name "unconnected-(U1A-PB9-Pad46)") (class "Default")
      (node (ref "U1") (pin "46") (pinfunction "PB9_46") (pintype "bidirectional+no_connect"))
    )
    (net (code "85") (name "unconnected-(U1A-PB10-Pad21)") (class "Default")
      (node (ref "U1") (pin "21") (pinfunction "PB10_21") (pintype "bidirectional+no_connect"))
    )
    (net (code "86") (name "unconnected-(U1A-PB11-Pad22)") (class "Default")
      (node (ref "U1") (pin "22") (pinfunction "PB11_22") (pintype "bidirectional+no_connect"))
    )
    (net (code "87") (name "unconnected-(U1A-PB15-Pad28)") (class "Default")
      (node (ref "U1") (pin "28") (pinfunction "PB15_28") (pintype "bidirectional+no_connect"))
    )
    (net (code "88") (name "unconnected-(U1A-PC15-OSC32_OUT-Pad4)") (class "Default")
      (node (ref "U1") (pin "4") (pinfunction "PC15-OSC32_OUT_4") (pintype "bidirectional+no_connect"))
    )
    (net (code "89") (name "unconnected-(U2-PA0-Pad12)") (class "Default")
      (node (ref "U2") (pin "12") (pinfunction "PA0_12") (pintype "bidirectional+no_connect"))
    )
    (net (code "90") (name "unconnected-(U2-PA1-Pad13)") (class "Default")
      (node (ref "U2") (pin "13") (pinfunction "PA1_13") (pintype "bidirectional+no_connect"))
    )
    (net (code "91") (name "unconnected-(U2-PA2-Pad14)") (class "Default")
      (node (ref "U2") (pin "14") (pinfunction "PA2_14") (pintype "bidirectional+no_connect"))
    )
    (net (code "92") (name "unconnected-(U2-PA3-Pad17)") (class "Default")
      (node (ref "U2") (pin "17") (pinfunction "PA3_17") (pintype "bidirectional+no_connect"))
    )
    (net (code "93") (name "unconnected-(U2-PA8-Pad42)") (class "Default")
      (node (ref "U2") (pin "42") (pinfunction "PA8_42") (pintype "bidirectional+no_connect"))
    )
    (net (code "94") (name "unconnected-(U2-PA15-Pad51)") (class "Default")
      (node (ref "U2") (pin "51") (pinfunction "PA15_51") (pintype "bidirectional+no_connect"))
    )
    (net (code "95") (name "unconnected-(U2-PB0-Pad24)") (class "Default")
      (node (ref "U2") (pin "24") (pinfunction "PB0_24") (pintype "bidirectional+no_connect"))
    )
    (net (code "96") (name "unconnected-(U2-PB1-Pad25)") (class "Default")
      (node (ref "U2") (pin "25") (pinfunction "PB1_25") (pintype "bidirectional+no_connect"))
    )
    (net (code "97") (name "unconnected-(U2-PB2-Pad26)") (class "Default")
      (node (ref "U2") (pin "26") (pinfunction "PB2_26") (pintype "bidirectional+no_connect"))
    )
    (net (code "98") (name "unconnected-(U2-PB3-Pad56)") (class "Default")
      (node (ref "U2") (pin "56") (pinfunction "PB3_56") (pintype "bidirectional+no_connect"))
    )
    (net (code "99") (name "unconnected-(U2-PB5-Pad58)") (class "Default")
      (node (ref "U2") (pin "58") (pinfunction "PB5_58") (pintype "bidirectional+no_connect"))
    )
    (net (code "100") (name "unconnected-(U2-PB7-Pad60)") (class "Default")
      (node (ref "U2") (pin "60") (pinfunction "PB7_60") (pintype "bidirectional+no_connect"))
    )
    (net (code "101") (name "unconnected-(U2-PB9-Pad62)") (class "Default")
      (node (ref "U2") (pin "62") (pinfunction "PB9_62") (pintype "bidirectional+no_connect"))
    )
    (net (code "102") (name "unconnected-(U2-PB10-Pad30)") (class "Default")
      (node (ref "U2") (pin "30") (pinfunction "PB10_30") (pintype "bidirectional+no_connect"))
    )
    (net (code "103") (name "unconnected-(U2-PB12-Pad34)") (class "Default")
      (node (ref "U2") (pin "34") (pinfunction "PB12_34") (pintype "bidirectional+no_connect"))
    )
    (net (code "104") (name "unconnected-(U2-PB13-Pad35)") (class "Default")
      (node (ref "U2") (pin "35") (pinfunction "PB13_35") (pintype "bidirectional+no_connect"))
    )
    (net (code "105") (name "unconnected-(U2-PB14-Pad36)") (class "Default")
      (node (ref "U2") (pin "36") (pinfunction "PB14_36") (pintype "bidirectional+no_connect"))
    )
    (net (code "106") (name "unconnected-(U2-PB15-Pad37)") (class "Default")
      (node (ref "U2") (pin "37") (pinfunction "PB15_37") (pintype "bidirectional+no_connect"))
    )
    (net (code "107") (name "unconnected-(U2-PC2-Pad10)") (class "Default")
      (node (ref "U2") (pin "10") (pinfunction "PC2_10") (pintype "bidirectional+no_connect"))
    )
    (net (code "108") (name "unconnected-(U2-PC3-Pad11)") (class "Default")
      (node (ref "U2") (pin "11") (pinfunction "PC3_11") (pintype "bidirectional+no_connect"))
    )
    (net (code "109") (name "unconnected-(U2-PC5-Pad23)") (class "Default")
      (node (ref "U2") (pin "23") (pinfunction "PC5_23") (pintype "bidirectional+no_connect"))
    )
    (net (code "110") (name "unconnected-(U2-PC10-Pad52)") (class "Default")
      (node (ref "U2") (pin "52") (pinfunction "PC10_52") (pintype "bidirectional+no_connect"))
    )
    (net (code "111") (name "unconnected-(U2-PC11-Pad53)") (class "Default")
      (node (ref "U2") (pin "53") (pinfunction "PC11_53") (pintype "bidirectional+no_connect"))
    )
    (net (code "112") (name "unconnected-(U2-PC12-Pad54)") (class "Default")
      (node (ref "U2") (pin "54") (pinfunction "PC12_54") (pintype "bidirectional+no_connect"))
    )
    (net (code "113") (name "unconnected-(U2-PC14-OSC32_IN-Pad3)") (class "Default")
      (node (ref "U2") (pin "3") (pinfunction "PC14-OSC32_IN_3") (pintype "bidirectional+no_connect"))
    )
    (net (code "114") (name "unconnected-(U2-PC15-OSC32_OUT-Pad4)") (class "Default")
      (node (ref "U2") (pin "4") (pinfunction "PC15-OSC32_OUT_4") (pintype "bidirectional+no_connect"))
    )
    (net (code "115") (name "unconnected-(U2-PD2-Pad55)") (class "Default")
      (node (ref "U2") (pin "55") (pinfunction "PD2_55") (pintype "bidirectional+no_connect"))
    )
    (net (code "116") (name "unconnected-(U3-NC-Pad4)") (class "Default")
      (node (ref "U3") (pin "4") (pinfunction "NC_4") (pintype "passive+no_connect"))
    )
    (net (code "117") (name "unconnected-(USBC1-SBU1-PadA8)") (class "Default")
      (node (ref "USBC1") (pin "A8") (pinfunction "SBU1_A8") (pintype "passive+no_connect"))
    )
    (net (code "118") (name "unconnected-(USBC1-SBU2-PadB8)") (class "Default")
      (node (ref "USBC1") (pin "B8") (pinfunction "SBU2_B8") (pintype "passive+no_connect"))
    )
    (net (code "119") (name "unconnected-(USBC2-SBU1-PadA8)") (class "Default")
      (node (ref "USBC2") (pin "A8") (pinfunction "SBU1_A8") (pintype "passive+no_connect"))
    )
    (net (code "120") (name "unconnected-(USBC2-SBU2-PadB8)") (class "Default")
      (node (ref "USBC2") (pin "B8") (pinfunction "SBU2_B8") (pintype "passive+no_connect"))
    )
  )
)
